# 5V_7805.net
KiCad netlist of a schematic drawn in EAGLE
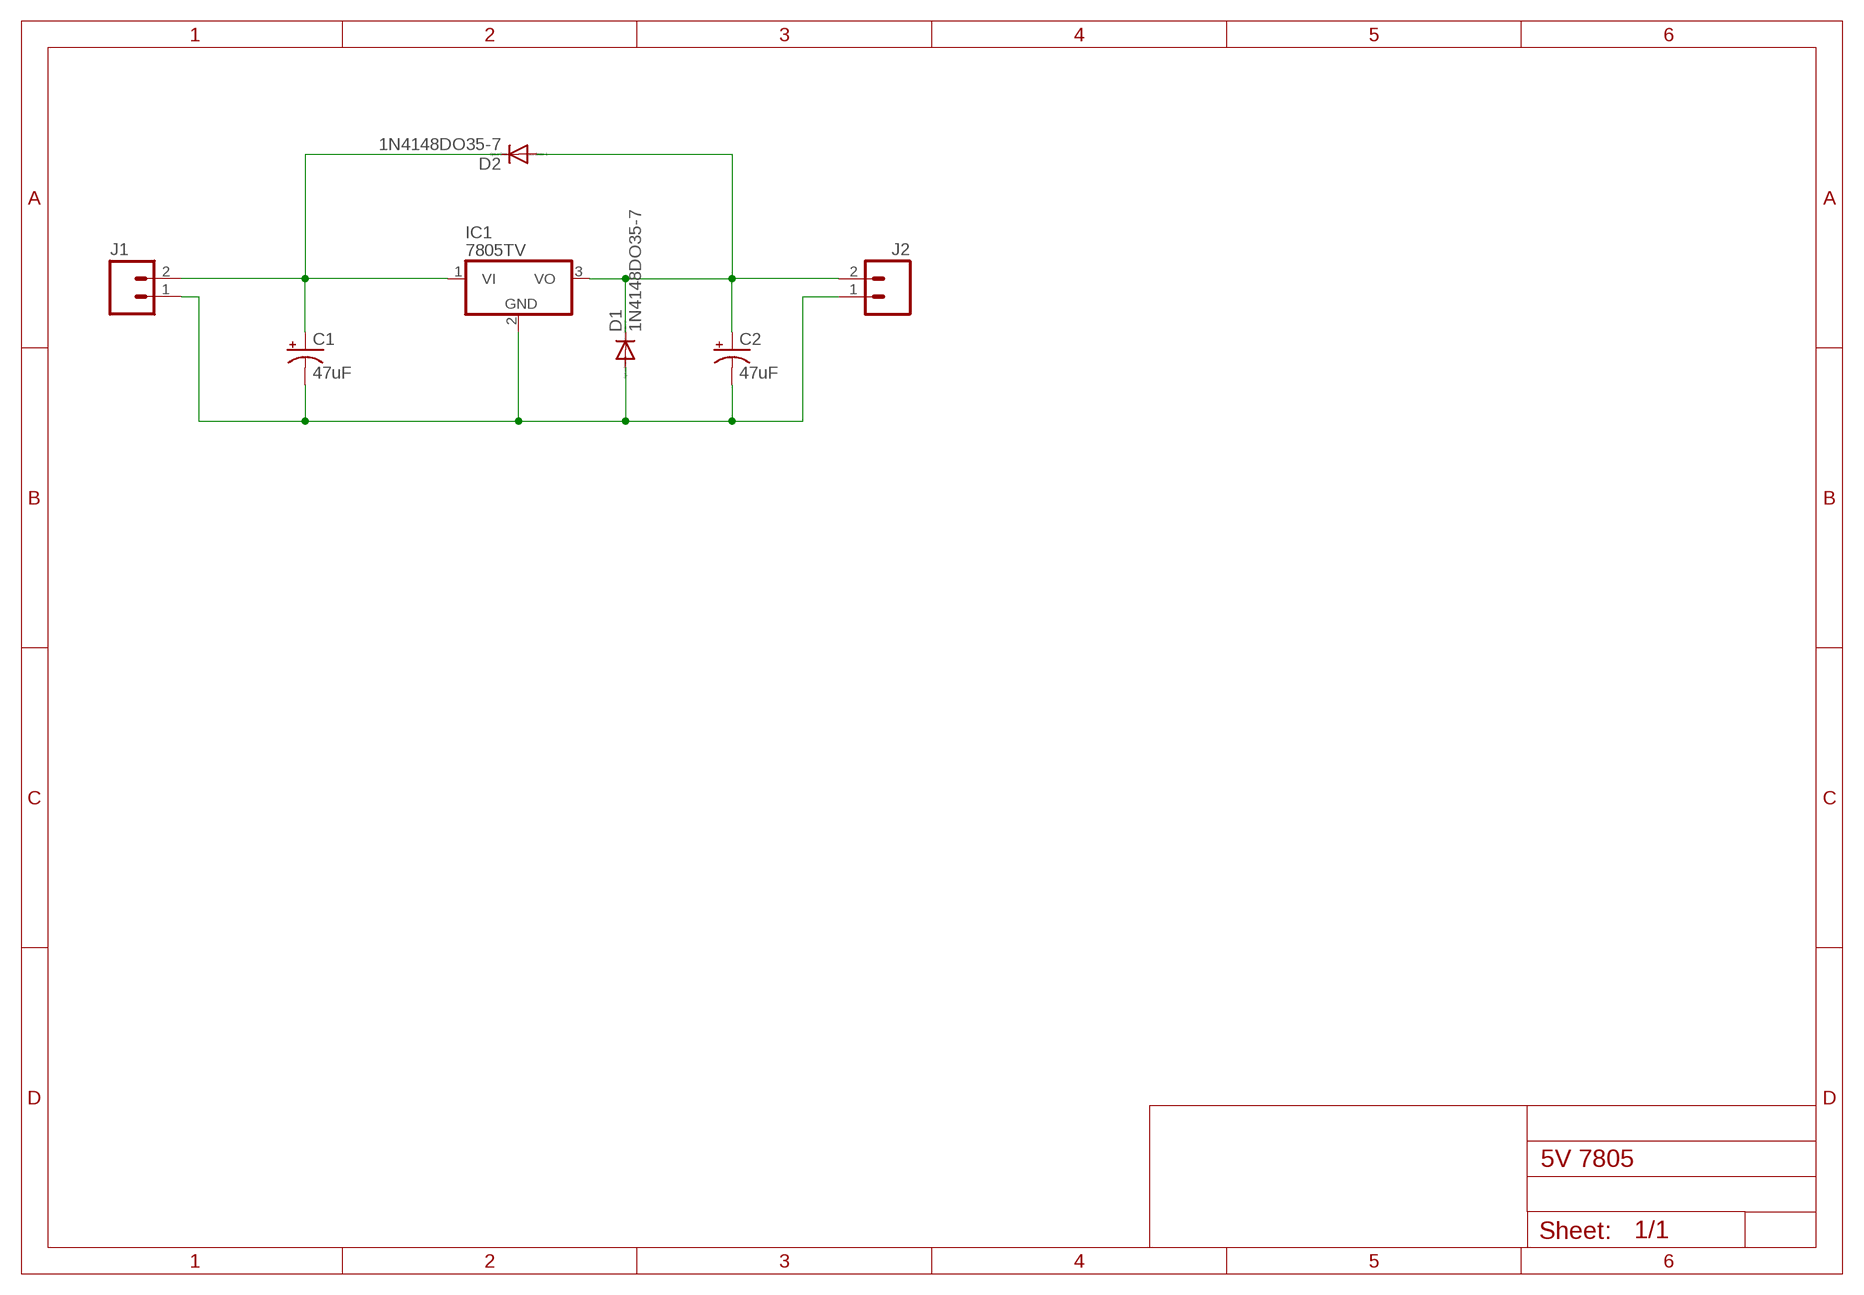
[diagram p0: schematic, sheet 1]

(export (version "E")
  (design (tool "Eeschema 10.0.6"))
  (components
    (comp (ref "C1")
      (value "47uF")
      (footprint "eagle-import:CPOL-RADIAL-100UF-25V")
      (libsource (lib "eagle-import") (part "100UF-25V-20%(PTH)"))
    )
    (comp (ref "C2")
      (value "47uF")
      (footprint "eagle-import:CPOL-RADIAL-100UF-25V")
      (libsource (lib "eagle-import") (part "100UF-25V-20%(PTH)"))
    )
    (comp (ref "D1")
      (value "1N4148DO35-7")
      (footprint "eagle-import:DO35-7")
      (libsource (lib "eagle-import") (part "1N4148DO35-7"))
    )
    (comp (ref "D2")
      (value "1N4148DO35-7")
      (footprint "eagle-import:DO35-7")
      (libsource (lib "eagle-import") (part "1N4148DO35-7"))
    )
    (comp (ref "IC1")
      (value "7805TV")
      (footprint "eagle-import:TO220V")
      (libsource (lib "eagle-import") (part "78TV05"))
    )
    (comp (ref "J1")
      (value "M025MM")
      (footprint "eagle-import:SCREWTERMINAL-5MM-2")
      (libsource (lib "eagle-import") (part "M025MM"))
    )
    (comp (ref "J2")
      (value "M025MM")
      (footprint "eagle-import:SCREWTERMINAL-5MM-2")
      (libsource (lib "eagle-import") (part "M025MM"))
    )
  )
  (nets
    (net (code "1") (name "Net-(C1-+)") (class "Default")
      (node (ref "C1") (pin "1") (pinfunction "+_1") (pintype "passive"))
      (node (ref "D2") (pin "C") (pinfunction "C_C") (pintype "passive"))
      (node (ref "IC1") (pin "1") (pinfunction "VI_1") (pintype "input"))
      (node (ref "J1") (pin "2") (pinfunction "2_2") (pintype "passive"))
    )
    (net (code "2") (name "Net-(C1--)") (class "Default")
      (node (ref "C1") (pin "2") (pinfunction "-_2") (pintype "passive"))
      (node (ref "C2") (pin "2") (pinfunction "-_2") (pintype "passive"))
      (node (ref "D1") (pin "A") (pinfunction "A_A") (pintype "passive"))
      (node (ref "IC1") (pin "2") (pinfunction "GND_2") (pintype "passive"))
      (node (ref "J1") (pin "1") (pinfunction "1_1") (pintype "passive"))
      (node (ref "J2") (pin "1") (pinfunction "1_1") (pintype "passive"))
    )
    (net (code "3") (name "Net-(C2-+)") (class "Default")
      (node (ref "C2") (pin "1") (pinfunction "+_1") (pintype "passive"))
      (node (ref "D1") (pin "C") (pinfunction "C_C") (pintype "passive"))
      (node (ref "D2") (pin "A") (pinfunction "A_A") (pintype "passive"))
      (node (ref "IC1") (pin "3") (pinfunction "VO_3") (pintype "passive"))
      (node (ref "J2") (pin "2") (pinfunction "2_2") (pintype "passive"))
    )
  )
)
